# SparkFun_Dev_ESP32_C3_MINI_-_PTH.net
KiCad netlist of a schematic drawn in EAGLE
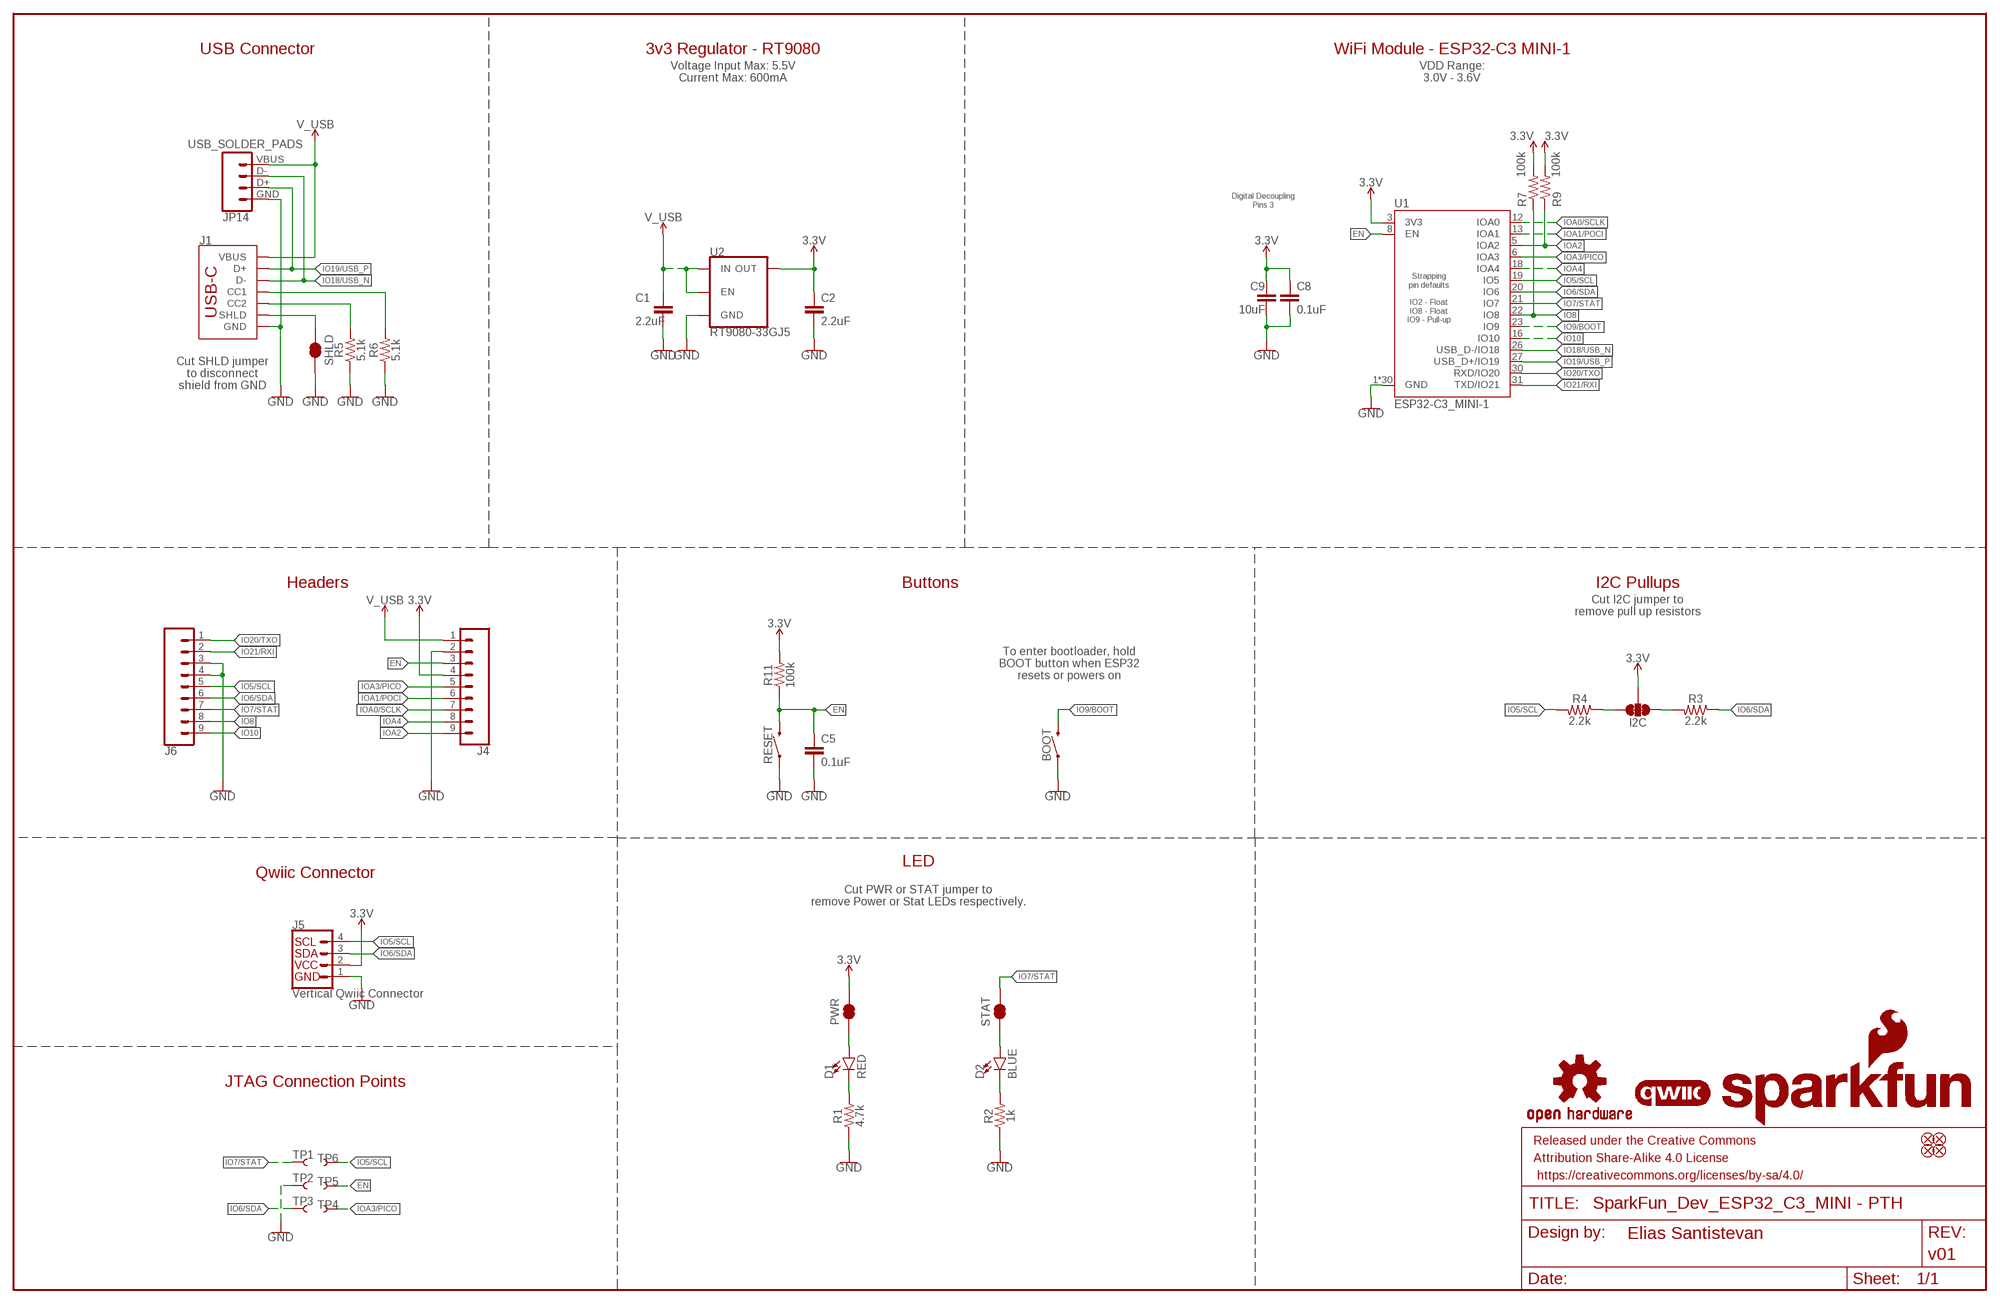
[diagram p0: schematic, sheet 1]

(export (version "E")
  (design (tool "Eeschema 10.0.6"))
  (components
    (comp (ref "BOOT")
      (value "MOMENTARY-SWITCH-SPST-SMD-4.6X2.8MM")
      (footprint "eagle-import:TACTILE_SWITCH_SMD_4.6X2.8MM")
      (libsource (lib "eagle-import") (part "MOMENTARY-SWITCH-SPST-SMD-4.6X2.8MM"))
    )
    (comp (ref "C1")
      (value "2.2uF")
      (footprint "eagle-import:0402-TIGHT")
      (libsource (lib "eagle-import") (part "2.2UF-0402_TIGHT-10V-10%-X5R"))
    )
    (comp (ref "C2")
      (value "2.2uF")
      (footprint "eagle-import:0402-TIGHT")
      (libsource (lib "eagle-import") (part "2.2UF-0402_TIGHT-10V-10%-X5R"))
    )
    (comp (ref "C5")
      (value "0.1uF")
      (footprint "eagle-import:0402-TIGHT")
      (libsource (lib "eagle-import") (part "0.1UF-0402T-6.3V-10%-X7R"))
    )
    (comp (ref "C8")
      (value "0.1uF")
      (footprint "eagle-import:0402-TIGHT")
      (libsource (lib "eagle-import") (part "0.1UF-0402T-16V-10%"))
    )
    (comp (ref "C9")
      (value "10uF")
      (footprint "eagle-import:0402-TIGHT")
      (libsource (lib "eagle-import") (part "10UF-0402T-6.3V-20%"))
    )
    (comp (ref "D1")
      (value "RED")
      (footprint "eagle-import:LED-0603")
      (libsource (lib "eagle-import") (part "LED-RED_0603-KB"))
    )
    (comp (ref "D2")
      (value "BLUE")
      (footprint "eagle-import:LED-0603")
      (libsource (lib "eagle-import") (part "LED-BLUE0603"))
    )
    (comp (ref "FD1")
      (value "FIDUCIALUFIDUCIAL")
      (footprint "eagle-import:FIDUCIAL-MICRO")
      (libsource (lib "eagle-import") (part "FIDUCIALUFIDUCIAL"))
    )
    (comp (ref "FD2")
      (value "FIDUCIALUFIDUCIAL")
      (footprint "eagle-import:FIDUCIAL-MICRO")
      (libsource (lib "eagle-import") (part "FIDUCIALUFIDUCIAL"))
    )
    (comp (ref "FD3")
      (value "FIDUCIALUFIDUCIAL")
      (footprint "eagle-import:FIDUCIAL-MICRO")
      (libsource (lib "eagle-import") (part "FIDUCIALUFIDUCIAL"))
    )
    (comp (ref "FD4")
      (value "FIDUCIALUFIDUCIAL")
      (footprint "eagle-import:FIDUCIAL-MICRO")
      (libsource (lib "eagle-import") (part "FIDUCIALUFIDUCIAL"))
    )
    (comp (ref "FRAME2")
      (value "FRAME-LEDGER")
      (footprint "eagle-import:CREATIVE_COMMONS")
      (fields (field (name "DESIGNER") "Elias Santistevan") (field (name "REV") "v01"))
      (libsource (lib "eagle-import") (part "FRAME-LEDGER"))
    )
    (comp (ref "I2C")
      (value "JUMPER-SMT_3_2-NC_TRACE_SILK")
      (footprint "eagle-import:SMT-JUMPER_3_2-NC_TRACE_SILK")
      (libsource (lib "eagle-import") (part "JUMPER-SMT_3_2-NC_TRACE_SILK"))
    )
    (comp (ref "J1")
      (value "USB Female Type C Connector")
      (footprint "eagle-import:USB-C-16P_4LAYER-PADS")
      (libsource (lib "eagle-import") (part "USB_C_4-LAYER_PADS"))
    )
    (comp (ref "J4")
      (value "CONN_09NO_SILK")
      (footprint "eagle-import:1X09_NO_SILK")
      (libsource (lib "eagle-import") (part "CONN_09NO_SILK"))
    )
    (comp (ref "J5")
      (value "Vertical Qwiic Connector")
      (footprint "eagle-import:JST04_1MM_VERT")
      (libsource (lib "eagle-import") (part "QWIIC_CONNECTOR"))
    )
    (comp (ref "J6")
      (value "CONN_09NO_SILK")
      (footprint "eagle-import:1X09_NO_SILK")
      (libsource (lib "eagle-import") (part "CONN_09NO_SILK"))
    )
    (comp (ref "JP14")
      (value "USB_SOLDER_PADS")
      (footprint "eagle-import:USB-SOLDER-PADS")
      (libsource (lib "eagle-import") (part "USB_SOLDER_PADS"))
    )
    (comp (ref "LOGO1")
      (value "SFE_LOGO_NAME_FLAMEBLANK")
      (footprint "eagle-import:BLANK")
      (libsource (lib "eagle-import") (part "SFE_LOGO_NAME_FLAMEBLANK"))
    )
    (comp (ref "LOGO2")
      (value "QWIIC_LOGO_3MM")
      (footprint "eagle-import:QWIIC_3MM")
      (libsource (lib "eagle-import") (part "QWIIC_LOGO_3MM"))
    )
    (comp (ref "LOGO3")
      (value "OSHW-LOGOS")
      (footprint "eagle-import:OSHW-LOGO-S")
      (libsource (lib "eagle-import") (part "OSHW-LOGOS"))
    )
    (comp (ref "PWR")
      (value "JUMPER-SMT_2_NC_TRACE_SILK")
      (footprint "eagle-import:SMT-JUMPER_2_NC_TRACE_SILK")
      (libsource (lib "eagle-import") (part "JUMPER-SMT_2_NC_TRACE_SILK"))
    )
    (comp (ref "R1")
      (value "4.7k")
      (footprint "eagle-import:0402-TIGHT")
      (libsource (lib "eagle-import") (part "4.7KOHM-0402T-1/16W-1%"))
    )
    (comp (ref "R2")
      (value "1k")
      (footprint "eagle-import:0402-TIGHT")
      (libsource (lib "eagle-import") (part "1KOHM-0402T-1/16W-1%"))
    )
    (comp (ref "R3")
      (value "2.2k")
      (footprint "eagle-import:0402-TIGHT")
      (libsource (lib "eagle-import") (part "2.2KOHM-0402T-1/16W-1%"))
    )
    (comp (ref "R4")
      (value "2.2k")
      (footprint "eagle-import:0402-TIGHT")
      (libsource (lib "eagle-import") (part "2.2KOHM-0402T-1/16W-1%"))
    )
    (comp (ref "R5")
      (value "5.1k")
      (footprint "eagle-import:0402-TIGHT")
      (libsource (lib "eagle-import") (part "5.1KOHM-0402T-1/16W-1%"))
    )
    (comp (ref "R6")
      (value "5.1k")
      (footprint "eagle-import:0402-TIGHT")
      (libsource (lib "eagle-import") (part "5.1KOHM-0402T-1/16W-1%"))
    )
    (comp (ref "R7")
      (value "100k")
      (footprint "eagle-import:0402-TIGHT")
      (libsource (lib "eagle-import") (part "100KOHM-0402T-1/16W-1%"))
    )
    (comp (ref "R9")
      (value "100k")
      (footprint "eagle-import:0402-TIGHT")
      (libsource (lib "eagle-import") (part "100KOHM-0402T-1/16W-1%"))
    )
    (comp (ref "R11")
      (value "100k")
      (footprint "eagle-import:0402-TIGHT")
      (libsource (lib "eagle-import") (part "100KOHM-0402T-1/16W-1%"))
    )
    (comp (ref "RESET")
      (value "MOMENTARY-SWITCH-SPST-SMD-4.6X2.8MM")
      (footprint "eagle-import:TACTILE_SWITCH_SMD_4.6X2.8MM")
      (libsource (lib "eagle-import") (part "MOMENTARY-SWITCH-SPST-SMD-4.6X2.8MM"))
    )
    (comp (ref "SHLD")
      (value "JUMPER-SMT_2_NC_TRACE_SILK")
      (footprint "eagle-import:SMT-JUMPER_2_NC_TRACE_SILK")
      (libsource (lib "eagle-import") (part "JUMPER-SMT_2_NC_TRACE_SILK"))
    )
    (comp (ref "STAT")
      (value "JUMPER-SMT_2_NC_TRACE_SILK")
      (footprint "eagle-import:SMT-JUMPER_2_NC_TRACE_SILK")
      (libsource (lib "eagle-import") (part "JUMPER-SMT_2_NC_TRACE_SILK"))
    )
    (comp (ref "TP1")
      (value "TEST-POINT3X5")
      (footprint "eagle-import:PAD.03X.05")
      (libsource (lib "eagle-import") (part "TEST-POINT3X5"))
    )
    (comp (ref "TP2")
      (value "TEST-POINT3X5")
      (footprint "eagle-import:PAD.03X.05")
      (libsource (lib "eagle-import") (part "TEST-POINT3X5"))
    )
    (comp (ref "TP3")
      (value "TEST-POINT3X5")
      (footprint "eagle-import:PAD.03X.05")
      (libsource (lib "eagle-import") (part "TEST-POINT3X5"))
    )
    (comp (ref "TP4")
      (value "TEST-POINT3X5")
      (footprint "eagle-import:PAD.03X.05")
      (libsource (lib "eagle-import") (part "TEST-POINT3X5"))
    )
    (comp (ref "TP5")
      (value "TEST-POINT3X5")
      (footprint "eagle-import:PAD.03X.05")
      (libsource (lib "eagle-import") (part "TEST-POINT3X5"))
    )
    (comp (ref "TP6")
      (value "TEST-POINT3X5")
      (footprint "eagle-import:PAD.03X.05")
      (libsource (lib "eagle-import") (part "TEST-POINT3X5"))
    )
    (comp (ref "U1")
      (value "ESP32-C3_MINI-1")
      (footprint "eagle-import:ESP32-C3-MINI-1")
      (libsource (lib "eagle-import") (part "ESP32-C3_MINI-1"))
    )
    (comp (ref "U2")
      (value "RT9080-33GJ5")
      (footprint "eagle-import:SOT23-5")
      (libsource (lib "eagle-import") (part "V_REG_RT9080"))
    )
  )
  (nets
    (net (code "1") (name "3.3V") (class "Default")
      (node (ref "C2") (pin "1") (pinfunction "1_1") (pintype "passive"))
      (node (ref "C8") (pin "1") (pinfunction "1_1") (pintype "passive"))
      (node (ref "C9") (pin "1") (pinfunction "1_1") (pintype "passive"))
      (node (ref "I2C") (pin "2") (pinfunction "2_2") (pintype "passive"))
      (node (ref "J4") (pin "4") (pinfunction "4_4") (pintype "passive"))
      (node (ref "J5") (pin "2") (pinfunction "2_2") (pintype "power_in"))
      (node (ref "PWR") (pin "2") (pinfunction "2_2") (pintype "passive"))
      (node (ref "R11") (pin "2") (pinfunction "2_2") (pintype "passive"))
      (node (ref "R7") (pin "2") (pinfunction "2_2") (pintype "passive"))
      (node (ref "R9") (pin "2") (pinfunction "2_2") (pintype "passive"))
      (node (ref "U1") (pin "3") (pinfunction "3V3_3") (pintype "bidirectional"))
      (node (ref "U2") (pin "5") (pinfunction "OUT_5") (pintype "passive"))
    )
    (net (code "2") (name "EN") (class "Default")
      (node (ref "C5") (pin "1") (pinfunction "1_1") (pintype "passive"))
      (node (ref "J4") (pin "3") (pinfunction "3_3") (pintype "passive"))
      (node (ref "R11") (pin "1") (pinfunction "1_1") (pintype "passive"))
      (node (ref "RESET") (pin "3") (pinfunction "2_3") (pintype "passive"))
      (node (ref "RESET") (pin "4") (pinfunction "2_4") (pintype "passive"))
      (node (ref "TP5") (pin "1") (pinfunction "1_1") (pintype "bidirectional"))
      (node (ref "U1") (pin "8") (pinfunction "EN_8") (pintype "bidirectional"))
    )
    (net (code "3") (name "GND") (class "Default")
      (node (ref "BOOT") (pin "1") (pinfunction "1_1") (pintype "passive"))
      (node (ref "BOOT") (pin "2") (pinfunction "1_2") (pintype "passive"))
      (node (ref "C1") (pin "2") (pinfunction "2_2") (pintype "passive"))
      (node (ref "C2") (pin "2") (pinfunction "2_2") (pintype "passive"))
      (node (ref "C5") (pin "2") (pinfunction "2_2") (pintype "passive"))
      (node (ref "C8") (pin "2") (pinfunction "2_2") (pintype "passive"))
      (node (ref "C9") (pin "2") (pinfunction "2_2") (pintype "passive"))
      (node (ref "J1") (pin "GND") (pinfunction "GND_GND") (pintype "bidirectional"))
      (node (ref "J1") (pin "GND2") (pinfunction "GND_GND2") (pintype "bidirectional"))
      (node (ref "J4") (pin "2") (pinfunction "2_2") (pintype "passive"))
      (node (ref "J5") (pin "1") (pinfunction "1_1") (pintype "power_in"))
      (node (ref "J6") (pin "3") (pinfunction "3_3") (pintype "passive"))
      (node (ref "J6") (pin "4") (pinfunction "4_4") (pintype "passive"))
      (node (ref "JP14") (pin "GND") (pinfunction "4_GND") (pintype "passive"))
      (node (ref "R1") (pin "1") (pinfunction "1_1") (pintype "passive"))
      (node (ref "R2") (pin "1") (pinfunction "1_1") (pintype "passive"))
      (node (ref "R5") (pin "1") (pinfunction "1_1") (pintype "passive"))
      (node (ref "R6") (pin "1") (pinfunction "1_1") (pintype "passive"))
      (node (ref "RESET") (pin "1") (pinfunction "1_1") (pintype "passive"))
      (node (ref "RESET") (pin "2") (pinfunction "1_2") (pintype "passive"))
      (node (ref "SHLD") (pin "2") (pinfunction "2_2") (pintype "passive"))
      (node (ref "TP2") (pin "1") (pinfunction "1_1") (pintype "bidirectional"))
      (node (ref "U1") (pin "1") (pinfunction "GND_1") (pintype "bidirectional"))
      (node (ref "U1") (pin "11") (pinfunction "GND_11") (pintype "bidirectional"))
      (node (ref "U1") (pin "14") (pinfunction "GND_14") (pintype "bidirectional"))
      (node (ref "U1") (pin "2") (pinfunction "GND_2") (pintype "bidirectional"))
      (node (ref "U1") (pin "36") (pinfunction "GND_36") (pintype "bidirectional"))
      (node (ref "U1") (pin "37") (pinfunction "GND_37") (pintype "bidirectional"))
      (node (ref "U1") (pin "38") (pinfunction "GND_38") (pintype "bidirectional"))
      (node (ref "U1") (pin "39") (pinfunction "GND_39") (pintype "bidirectional"))
      (node (ref "U1") (pin "40") (pinfunction "GND_40") (pintype "bidirectional"))
      (node (ref "U1") (pin "41") (pinfunction "GND_41") (pintype "bidirectional"))
      (node (ref "U1") (pin "42") (pinfunction "GND_42") (pintype "bidirectional"))
      (node (ref "U1") (pin "43") (pinfunction "GND_43") (pintype "bidirectional"))
      (node (ref "U1") (pin "44") (pinfunction "GND_44") (pintype "bidirectional"))
      (node (ref "U1") (pin "45") (pinfunction "GND_45") (pintype "bidirectional"))
      (node (ref "U1") (pin "46") (pinfunction "GND_46") (pintype "bidirectional"))
      (node (ref "U1") (pin "47") (pinfunction "GND_47") (pintype "bidirectional"))
      (node (ref "U1") (pin "48") (pinfunction "GND_48") (pintype "bidirectional"))
      (node (ref "U1") (pin "49.1") (pinfunction "GND_49.1") (pintype "bidirectional"))
      (node (ref "U1") (pin "49.2") (pinfunction "GND_49.2") (pintype "bidirectional"))
      (node (ref "U1") (pin "49.3") (pinfunction "GND_49.3") (pintype "bidirectional"))
      (node (ref "U1") (pin "49.4") (pinfunction "GND_49.4") (pintype "bidirectional"))
      (node (ref "U1") (pin "49.5") (pinfunction "GND_49.5") (pintype "bidirectional"))
      (node (ref "U1") (pin "49.6") (pinfunction "GND_49.6") (pintype "bidirectional"))
      (node (ref "U1") (pin "49.7") (pinfunction "GND_49.7") (pintype "bidirectional"))
      (node (ref "U1") (pin "49.8") (pinfunction "GND_49.8") (pintype "bidirectional"))
      (node (ref "U1") (pin "49.9") (pinfunction "GND_49.9") (pintype "bidirectional"))
      (node (ref "U1") (pin "50") (pinfunction "GND_50") (pintype "bidirectional"))
      (node (ref "U1") (pin "51") (pinfunction "GND_51") (pintype "bidirectional"))
      (node (ref "U1") (pin "52") (pinfunction "GND_52") (pintype "bidirectional"))
      (node (ref "U1") (pin "53") (pinfunction "GND_53") (pintype "bidirectional"))
      (node (ref "U2") (pin "2") (pinfunction "GND_2") (pintype "input"))
    )
    (net (code "4") (name "IO5{slash}SCL") (class "Default")
      (node (ref "J5") (pin "4") (pinfunction "4_4") (pintype "passive"))
      (node (ref "J6") (pin "5") (pinfunction "5_5") (pintype "passive"))
      (node (ref "R4") (pin "2") (pinfunction "2_2") (pintype "passive"))
      (node (ref "TP6") (pin "1") (pinfunction "1_1") (pintype "bidirectional"))
      (node (ref "U1") (pin "19") (pinfunction "IO5_19") (pintype "bidirectional"))
    )
    (net (code "5") (name "IO6{slash}SDA") (class "Default")
      (node (ref "J5") (pin "3") (pinfunction "3_3") (pintype "passive"))
      (node (ref "J6") (pin "6") (pinfunction "6_6") (pintype "passive"))
      (node (ref "R3") (pin "1") (pinfunction "1_1") (pintype "passive"))
      (node (ref "TP3") (pin "1") (pinfunction "1_1") (pintype "bidirectional"))
      (node (ref "U1") (pin "20") (pinfunction "IO6_20") (pintype "bidirectional"))
    )
    (net (code "6") (name "IO7{slash}STAT") (class "Default")
      (node (ref "J6") (pin "7") (pinfunction "7_7") (pintype "passive"))
      (node (ref "STAT") (pin "2") (pinfunction "2_2") (pintype "passive"))
      (node (ref "TP1") (pin "1") (pinfunction "1_1") (pintype "bidirectional"))
      (node (ref "U1") (pin "21") (pinfunction "IO7_21") (pintype "bidirectional"))
    )
    (net (code "7") (name "IO8") (class "Default")
      (node (ref "J6") (pin "8") (pinfunction "8_8") (pintype "passive"))
      (node (ref "R7") (pin "1") (pinfunction "1_1") (pintype "passive"))
      (node (ref "U1") (pin "22") (pinfunction "IO8_22") (pintype "bidirectional"))
    )
    (net (code "8") (name "IO9{slash}BOOT") (class "Default")
      (node (ref "BOOT") (pin "3") (pinfunction "2_3") (pintype "passive"))
      (node (ref "BOOT") (pin "4") (pinfunction "2_4") (pintype "passive"))
      (node (ref "U1") (pin "23") (pinfunction "IO9_23") (pintype "bidirectional"))
    )
    (net (code "9") (name "IO10") (class "Default")
      (node (ref "J6") (pin "9") (pinfunction "9_9") (pintype "passive"))
      (node (ref "U1") (pin "16") (pinfunction "IO10_16") (pintype "bidirectional"))
    )
    (net (code "10") (name "IO18{slash}USB_N") (class "Default")
      (node (ref "J1") (pin "A7") (pinfunction "D-_A7") (pintype "bidirectional"))
      (node (ref "J1") (pin "B7") (pinfunction "D-_B7") (pintype "bidirectional"))
      (node (ref "JP14") (pin "D-") (pinfunction "2_D-") (pintype "passive"))
      (node (ref "U1") (pin "26") (pinfunction "USB_D-/IO18_26") (pintype "bidirectional"))
    )
    (net (code "11") (name "IO19{slash}USB_P") (class "Default")
      (node (ref "J1") (pin "A6") (pinfunction "D+_A6") (pintype "bidirectional"))
      (node (ref "J1") (pin "B6") (pinfunction "D+_B6") (pintype "bidirectional"))
      (node (ref "JP14") (pin "D+") (pinfunction "3_D+") (pintype "passive"))
      (node (ref "U1") (pin "27") (pinfunction "USB_D+/IO19_27") (pintype "bidirectional"))
    )
    (net (code "12") (name "IO20{slash}TXO") (class "Default")
      (node (ref "J6") (pin "1") (pinfunction "1_1") (pintype "passive"))
      (node (ref "U1") (pin "30") (pinfunction "RXD/IO20_30") (pintype "bidirectional"))
    )
    (net (code "13") (name "IO21{slash}RXI") (class "Default")
      (node (ref "J6") (pin "2") (pinfunction "2_2") (pintype "passive"))
      (node (ref "U1") (pin "31") (pinfunction "TXD/IO21_31") (pintype "bidirectional"))
    )
    (net (code "14") (name "IOA0{slash}SCLK") (class "Default")
      (node (ref "J4") (pin "7") (pinfunction "7_7") (pintype "passive"))
      (node (ref "U1") (pin "12") (pinfunction "IOA0_12") (pintype "bidirectional"))
    )
    (net (code "15") (name "IOA1{slash}POCI") (class "Default")
      (node (ref "J4") (pin "6") (pinfunction "6_6") (pintype "passive"))
      (node (ref "U1") (pin "13") (pinfunction "IOA1_13") (pintype "bidirectional"))
    )
    (net (code "16") (name "IOA2") (class "Default")
      (node (ref "J4") (pin "9") (pinfunction "9_9") (pintype "passive"))
      (node (ref "R9") (pin "1") (pinfunction "1_1") (pintype "passive"))
      (node (ref "U1") (pin "5") (pinfunction "IOA2_5") (pintype "bidirectional"))
    )
    (net (code "17") (name "IOA3{slash}PICO") (class "Default")
      (node (ref "J4") (pin "5") (pinfunction "5_5") (pintype "passive"))
      (node (ref "TP4") (pin "1") (pinfunction "1_1") (pintype "bidirectional"))
      (node (ref "U1") (pin "6") (pinfunction "IOA3_6") (pintype "bidirectional"))
    )
    (net (code "18") (name "IOA4") (class "Default")
      (node (ref "J4") (pin "8") (pinfunction "8_8") (pintype "passive"))
      (node (ref "U1") (pin "18") (pinfunction "IOA4_18") (pintype "bidirectional"))
    )
    (net (code "19") (name "Net-(D1-PadA)") (class "Default")
      (node (ref "D1") (pin "A") (pinfunction "A_A") (pintype "passive"))
      (node (ref "PWR") (pin "1") (pinfunction "1_1") (pintype "passive"))
    )
    (net (code "20") (name "Net-(D1-PadC)") (class "Default")
      (node (ref "D1") (pin "C") (pinfunction "C_C") (pintype "passive"))
      (node (ref "R1") (pin "2") (pinfunction "2_2") (pintype "passive"))
    )
    (net (code "21") (name "Net-(D2-PadA)") (class "Default")
      (node (ref "D2") (pin "A") (pinfunction "A_A") (pintype "passive"))
      (node (ref "STAT") (pin "1") (pinfunction "1_1") (pintype "passive"))
    )
    (net (code "22") (name "Net-(D2-PadC)") (class "Default")
      (node (ref "D2") (pin "C") (pinfunction "C_C") (pintype "passive"))
      (node (ref "R2") (pin "2") (pinfunction "2_2") (pintype "passive"))
    )
    (net (code "23") (name "Net-(I2C-Pad1)") (class "Default")
      (node (ref "I2C") (pin "1") (pinfunction "1_1") (pintype "passive"))
      (node (ref "R4") (pin "1") (pinfunction "1_1") (pintype "passive"))
    )
    (net (code "24") (name "Net-(I2C-Pad3)") (class "Default")
      (node (ref "I2C") (pin "3") (pinfunction "3_3") (pintype "passive"))
      (node (ref "R3") (pin "2") (pinfunction "2_2") (pintype "passive"))
    )
    (net (code "25") (name "Net-(J1-CC1)") (class "Default")
      (node (ref "J1") (pin "A5") (pinfunction "CC1_A5") (pintype "bidirectional"))
      (node (ref "R6") (pin "2") (pinfunction "2_2") (pintype "passive"))
    )
    (net (code "26") (name "Net-(J1-CC2)") (class "Default")
      (node (ref "J1") (pin "B5") (pinfunction "CC2_B5") (pintype "bidirectional"))
      (node (ref "R5") (pin "2") (pinfunction "2_2") (pintype "passive"))
    )
    (net (code "27") (name "Net-(J1-SHLD-PadSHLD1)") (class "Default")
      (node (ref "J1") (pin "SHLD1") (pinfunction "SHLD_SHLD1") (pintype "bidirectional"))
      (node (ref "J1") (pin "SHLD2") (pinfunction "SHLD_SHLD2") (pintype "bidirectional"))
      (node (ref "J1") (pin "SHLD3") (pinfunction "SHLD_SHLD3") (pintype "bidirectional"))
      (node (ref "J1") (pin "SHLD4") (pinfunction "SHLD_SHLD4") (pintype "bidirectional"))
      (node (ref "SHLD") (pin "1") (pinfunction "1_1") (pintype "passive"))
    )
    (net (code "28") (name "V_USB") (class "Default")
      (node (ref "C1") (pin "1") (pinfunction "1_1") (pintype "passive"))
      (node (ref "J1") (pin "VBUS1") (pinfunction "VBUS_VBUS1") (pintype "bidirectional"))
      (node (ref "J1") (pin "VBUS2") (pinfunction "VBUS_VBUS2") (pintype "bidirectional"))
      (node (ref "J4") (pin "1") (pinfunction "1_1") (pintype "passive"))
      (node (ref "JP14") (pin "VBUS") (pinfunction "1_VBUS") (pintype "passive"))
      (node (ref "U2") (pin "1") (pinfunction "IN_1") (pintype "input"))
      (node (ref "U2") (pin "3") (pinfunction "EN_3") (pintype "input"))
    )
  )
)
